# MMC_2_4_Ethernet.net
KiCad netlist of a schematic drawn in Altium Designer
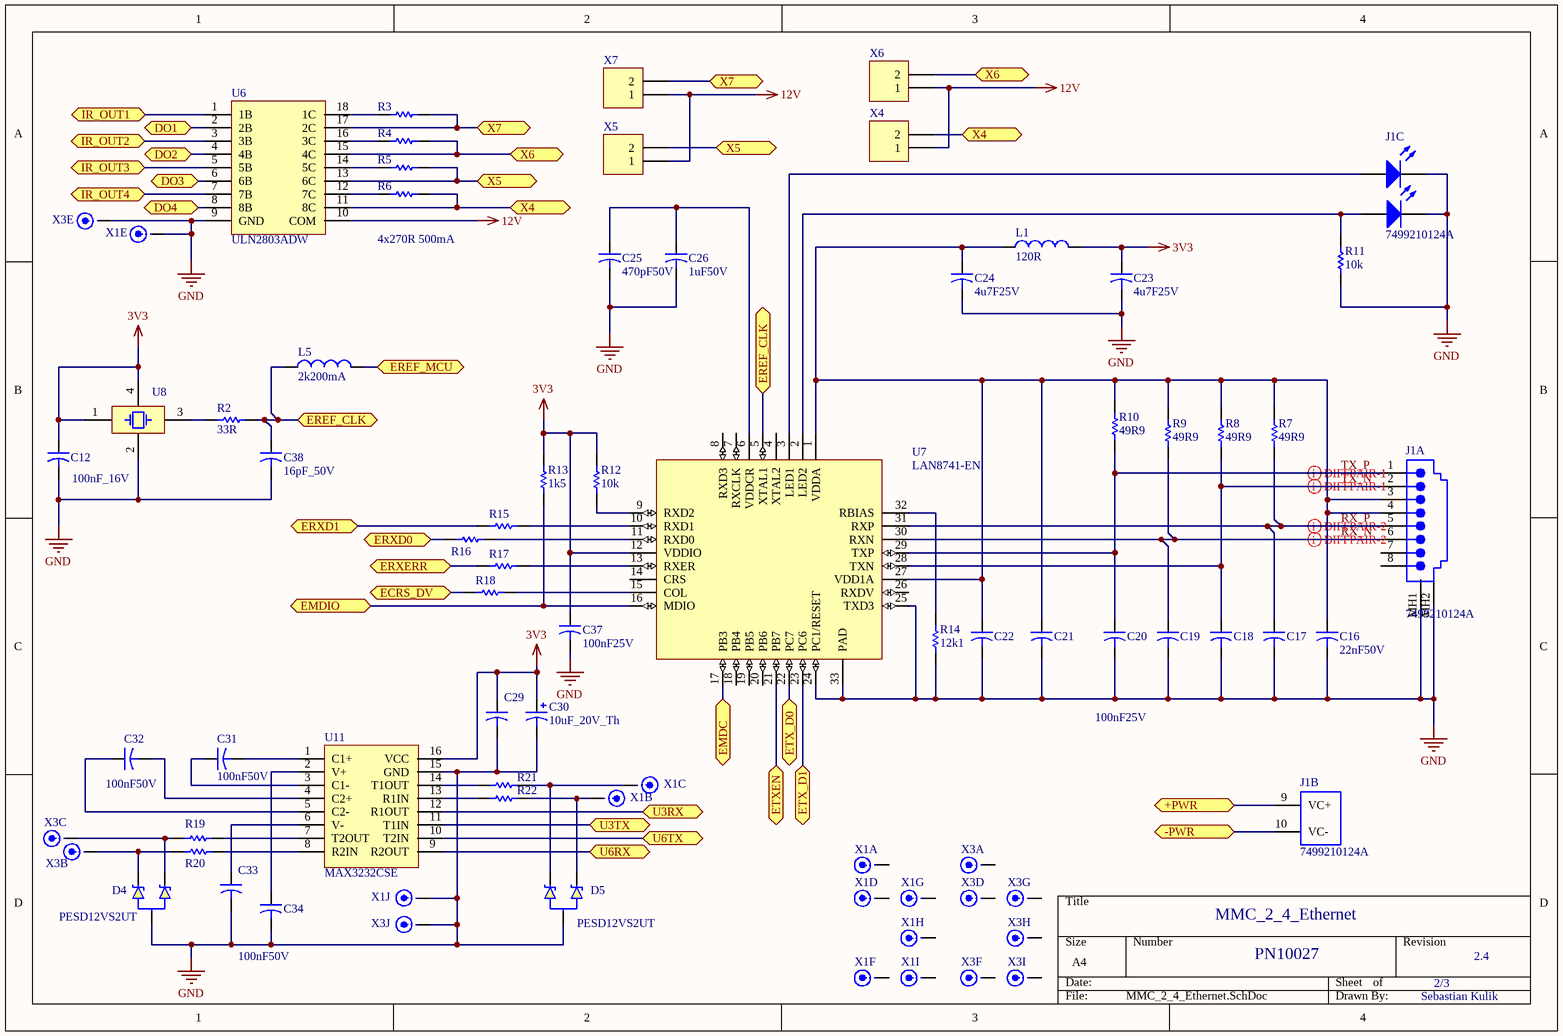
[diagram p0: MMC_2_4_Ethernet.SchDoc]

(export (version "E")
  (design (tool "Eeschema 10.0.6"))
  (components
    (comp (ref "C12")
      (value "100nF_16V")
      (footprint "C0402")
      (description "TDK. CGA series, X7R, 10%, 16V")
      (fields
        (field (name "MANUFACTURER") "TDK")
        (field (name "Comment") "100nF16V_0402")
        (field (name "PUBLISHER") "Sebastian Kulik")
      )
      (libsource (lib "Capacitors") (part "100nF16V_0402"))
    )
    (comp (ref "C16")
      (value "22nF50V")
      (footprint "C0603")
      (description "AVX ,  X7R, 5%, 50V")
      (fields
        (field (name "MANUFACTURER") "AVX")
        (field (name "Comment") "22nF50V_0603")
        (field (name "PUBLISHER") "Sebastian Kulik")
      )
      (libsource (lib "Capacitors") (part "22nF50V_0603"))
    )
    (comp (ref "C17")
      (value "10pF50V_0603")
      (footprint "C0603")
      (description "AVX ,  +-0.5pF, 50V")
      (fields (field (name "MANUFACTURER") "AVX") (field (name "PUBLISHER") "Sebastian Kulik"))
      (libsource (lib "Capacitors") (part "10pF50V_0603"))
    )
    (comp (ref "C18")
      (value "10pF50V_0603")
      (footprint "C0603")
      (description "AVX ,  +-0.5pF, 50V")
      (fields (field (name "MANUFACTURER") "AVX") (field (name "PUBLISHER") "Sebastian Kulik"))
      (libsource (lib "Capacitors") (part "10pF50V_0603"))
    )
    (comp (ref "C19")
      (value "10pF50V_0603")
      (footprint "C0603")
      (description "AVX ,  +-0.5pF, 50V")
      (fields (field (name "MANUFACTURER") "AVX") (field (name "PUBLISHER") "Sebastian Kulik"))
      (libsource (lib "Capacitors") (part "10pF50V_0603"))
    )
    (comp (ref "C20")
      (value "10pF50V_0603")
      (footprint "C0603")
      (description "AVX ,  +-0.5pF, 50V")
      (fields (field (name "MANUFACTURER") "AVX") (field (name "PUBLISHER") "Sebastian Kulik"))
      (libsource (lib "Capacitors") (part "10pF50V_0603"))
    )
    (comp (ref "C21")
      (value "100nF25V")
      (footprint "C0402")
      (description "AVX, X5R, 10%, 25V")
      (fields
        (field (name "MANUFACTURER") "AVX")
        (field (name "Comment") "100nF25V_0402")
        (field (name "PUBLISHER") "Sebastian Kulik")
      )
      (libsource (lib "Capacitors") (part "100nF25V_0402"))
    )
    (comp (ref "C22")
      (value "100nF25V_0402")
      (footprint "C0402")
      (description "AVX, X5R, 10%, 25V")
      (fields (field (name "MANUFACTURER") "AVX") (field (name "PUBLISHER") "Sebastian Kulik"))
      (libsource (lib "Capacitors") (part "100nF25V_0402"))
    )
    (comp (ref "C23")
      (value "4u7F25V")
      (footprint "C0805")
      (description "TDK  C series, X7R, 10%, 25V")
      (fields
        (field (name "MANUFACTURER") "TDK")
        (field (name "Comment") "4u7F25V_0805")
        (field (name "PUBLISHER") "Sebastian Kulik")
      )
      (libsource (lib "Capacitors") (part "4u7F25V_0805"))
    )
    (comp (ref "C24")
      (value "4u7F25V")
      (footprint "C0805")
      (description "TDK  C series, X7R, 10%, 25V")
      (fields
        (field (name "MANUFACTURER") "TDK")
        (field (name "Comment") "4u7F25V_0805")
        (field (name "PUBLISHER") "Sebastian Kulik")
      )
      (libsource (lib "Capacitors") (part "4u7F25V_0805"))
    )
    (comp (ref "C25")
      (value "470pF50V")
      (footprint "C0402")
      (description "AVX, 50V")
      (fields
        (field (name "MANUFACTURER") "AVX")
        (field (name "Comment") "470pF50V_0402")
        (field (name "PUBLISHER") "Sebastian Kulik")
      )
      (libsource (lib "Capacitors") (part "470pF50V_0402"))
    )
    (comp (ref "C26")
      (value "1uF50V")
      (footprint "C0603")
      (description "C series, X5R, 10%")
      (fields
        (field (name "MANUFACTURER") "TDK")
        (field (name "Comment") "1uF50V_0603")
        (field (name "PUBLISHER") "Sebastian Kulik")
      )
      (libsource (lib "Capacitors") (part "1uF50V_0603"))
    )
    (comp (ref "C29")
      (value "100nF25V_0402")
      (footprint "C0402")
      (description "AVX, X5R, 10%, 25V")
      (fields (field (name "MANUFACTURER") "AVX") (field (name "PUBLISHER") "Sebastian Kulik"))
      (libsource (lib "Capacitors") (part "100nF25V_0402"))
    )
    (comp (ref "C30")
      (value "10uF_20V_Th")
      (footprint "Vishay293D-B")
      (description "293 series, tantal, 10%, 10V")
      (fields
        (field (name "MANUFACTURER") "Vishay")
        (field (name "Comment") "10uF_20V_V293D-B")
        (field (name "PUBLISHER") "Sebastian Kulik")
      )
      (libsource (lib "Capacitors") (part "10uF_20V_V293D-B"))
    )
    (comp (ref "C31")
      (value "100nF50V")
      (footprint "C0402")
      (description "C series, X5R, 10%, 50V")
      (fields
        (field (name "MANUFACTURER") "Murata")
        (field (name "Comment") "100n50V_0402")
        (field (name "PUBLISHER") "Sebastian Kulik")
      )
      (libsource (lib "Capacitors") (part "100n50V_0402"))
    )
    (comp (ref "C32")
      (value "100nF50V")
      (footprint "C0402")
      (description "C series, X5R, 10%, 50V")
      (fields
        (field (name "MANUFACTURER") "Murata")
        (field (name "Comment") "100n50V_0402")
        (field (name "PUBLISHER") "Sebastian Kulik")
      )
      (libsource (lib "Capacitors") (part "100n50V_0402"))
    )
    (comp (ref "C33")
      (value "100n50V_0402")
      (footprint "C0402")
      (description "C series, X5R, 10%, 50V")
      (fields (field (name "MANUFACTURER") "Murata") (field (name "PUBLISHER") "Sebastian Kulik"))
      (libsource (lib "Capacitors") (part "100n50V_0402"))
    )
    (comp (ref "C34")
      (value "100nF50V")
      (footprint "C0402")
      (description "C series, X5R, 10%, 50V")
      (fields
        (field (name "MANUFACTURER") "Murata")
        (field (name "Comment") "100n50V_0402")
        (field (name "PUBLISHER") "Sebastian Kulik")
      )
      (libsource (lib "Capacitors") (part "100n50V_0402"))
    )
    (comp (ref "C37")
      (value "100nF25V")
      (footprint "C0402")
      (description "AVX, X5R, 10%, 25V")
      (fields
        (field (name "MANUFACTURER") "AVX")
        (field (name "Comment") "100nF25V_0402")
        (field (name "PUBLISHER") "Sebastian Kulik")
      )
      (libsource (lib "Capacitors") (part "100nF25V_0402"))
    )
    (comp (ref "C38")
      (value "16pF_50V")
      (footprint "C0402")
      (description "C series, 5%, 50V")
      (fields
        (field (name "MANUFACTURER") "Kemet")
        (field (name "Comment") "16pF50V_0402")
        (field (name "PUBLISHER") "Sebastian Kulik")
      )
      (libsource (lib "Capacitors") (part "16pF50V_0402"))
    )
    (comp (ref "D4")
      (value "PESD12VS2UT")
      (footprint "SOT23_N")
      (description "EDS diode(s)")
      (fields (field (name "MANUFACTURER") "NXP") (field (name "PUBLISHER") "Sebastian Kulik"))
      (libsource (lib "Discrete") (part "PESD12VS2UT"))
    )
    (comp (ref "D5")
      (value "PESD12VS2UT")
      (footprint "SOT23_N")
      (description "EDS diode(s)")
      (fields (field (name "MANUFACTURER") "NXP") (field (name "PUBLISHER") "Sebastian Kulik"))
      (libsource (lib "Discrete") (part "PESD12VS2UT"))
    )
    (comp (ref "J1")
      (value "7499210124A")
      (footprint "7499210124A")
      (description "Modular Jack , Right Angle RJ-45, Low Profile")
      (fields (field (name "MANUFACTURER") "Wuerth Elektronik") (field (name "PUBLISHER") "Sebastian Kulik"))
      (libsource (lib "Connectors") (part "Ethernet, POE, WE7499210124A"))
    )
    (comp (ref "L1")
      (value "120R")
      (footprint "L0603")
      (description "Murata, Ferrit, 120Rx2A")
      (fields
        (field (name "MANUFACTURER") "Murata")
        (field (name "Comment") "120R4A_0603")
        (field (name "PUBLISHER") "Sebastian Kulik")
      )
      (libsource (lib "Passives") (part "120R4A_0603"))
    )
    (comp (ref "L5")
      (value "2k200mA")
      (footprint "L0805_M")
      (description "Ferrit, 2k, 200mA")
      (fields
        (field (name "MANUFACTURER") "WE")
        (field (name "Comment") "2k200mA_0805")
        (field (name "PUBLISHER") "Sebastian Kulik")
      )
      (libsource (lib "Passives") (part "2k200mA_0805"))
    )
    (comp (ref "R2")
      (value "33R")
      (footprint "R0402")
      (description "Vishay CRCW series, 63mW, 1%")
      (fields
        (field (name "MANUFACTURER") "Vishay")
        (field (name "Comment") "33R_0402")
        (field (name "PUBLISHER") "Sebastian Kulik")
      )
      (libsource (lib "Resistors") (part "33R_0402"))
    )
    (comp (ref "R3")
      (value "270R_1210")
      (footprint "R1210_N")
      (description "ERJ series, 500mW, 5%")
      (fields (field (name "MANUFACTURER") "Panasonic") (field (name "PUBLISHER") "Sebastian Kulik"))
      (libsource (lib "Resistors") (part "270R_1210"))
    )
    (comp (ref "R4")
      (value "270R_1210")
      (footprint "R1210_N")
      (description "ERJ series, 500mW, 5%")
      (fields (field (name "MANUFACTURER") "Panasonic") (field (name "PUBLISHER") "Sebastian Kulik"))
      (libsource (lib "Resistors") (part "270R_1210"))
    )
    (comp (ref "R5")
      (value "270R_1210")
      (footprint "R1210_N")
      (description "ERJ series, 500mW, 5%")
      (fields (field (name "MANUFACTURER") "Panasonic") (field (name "PUBLISHER") "Sebastian Kulik"))
      (libsource (lib "Resistors") (part "270R_1210"))
    )
    (comp (ref "R6")
      (value "270R_1210")
      (footprint "R1210_N")
      (description "ERJ series, 500mW, 5%")
      (fields (field (name "MANUFACTURER") "Panasonic") (field (name "PUBLISHER") "Sebastian Kulik"))
      (libsource (lib "Resistors") (part "270R_1210"))
    )
    (comp (ref "R7")
      (value "49R9")
      (footprint "R0402")
      (description "Vishay CRCW series, 63mW, 1%")
      (fields
        (field (name "MANUFACTURER") "Vishay")
        (field (name "Comment") "49R9_0402")
        (field (name "PUBLISHER") "Sebastian Kulik")
      )
      (libsource (lib "Resistors") (part "49R9_0402"))
    )
    (comp (ref "R8")
      (value "49R9")
      (footprint "R0402")
      (description "Vishay CRCW series, 63mW, 1%")
      (fields
        (field (name "MANUFACTURER") "Vishay")
        (field (name "Comment") "49R9_0402")
        (field (name "PUBLISHER") "Sebastian Kulik")
      )
      (libsource (lib "Resistors") (part "49R9_0402"))
    )
    (comp (ref "R9")
      (value "49R9")
      (footprint "R0402")
      (description "Vishay CRCW series, 63mW, 1%")
      (fields
        (field (name "MANUFACTURER") "Vishay")
        (field (name "Comment") "49R9_0402")
        (field (name "PUBLISHER") "Sebastian Kulik")
      )
      (libsource (lib "Resistors") (part "49R9_0402"))
    )
    (comp (ref "R10")
      (value "49R9")
      (footprint "R0402")
      (description "Vishay CRCW series, 63mW, 1%")
      (fields
        (field (name "MANUFACTURER") "Vishay")
        (field (name "Comment") "49R9_0402")
        (field (name "PUBLISHER") "Sebastian Kulik")
      )
      (libsource (lib "Resistors") (part "49R9_0402"))
    )
    (comp (ref "R11")
      (value "10k")
      (footprint "R0402")
      (description "Vishay CRCW series, 125mW, 1%")
      (fields
        (field (name "MANUFACTURER") "Vishay")
        (field (name "Comment") "10k_0402")
        (field (name "PUBLISHER") "Sebastian Kulik")
      )
      (libsource (lib "Resistors") (part "10k_0402"))
    )
    (comp (ref "R12")
      (value "10k")
      (footprint "R0402")
      (description "Vishay CRCW series, 125mW, 1%")
      (fields
        (field (name "MANUFACTURER") "Vishay")
        (field (name "Comment") "10k_0402")
        (field (name "PUBLISHER") "Sebastian Kulik")
      )
      (libsource (lib "Resistors") (part "10k_0402"))
    )
    (comp (ref "R13")
      (value "1k5")
      (footprint "R0402")
      (description "Vishay CRCW series, 125mW, 1%")
      (fields
        (field (name "MANUFACTURER") "Vishay")
        (field (name "Comment") "1k5_0402")
        (field (name "PUBLISHER") "Sebastian Kulik")
      )
      (libsource (lib "Resistors") (part "1k5_0402"))
    )
    (comp (ref "R14")
      (value "12k1")
      (footprint "R0603(1608)")
      (description "Vishay, CRCW series, 100mW, 1%")
      (fields
        (field (name "MANUFACTURER") "Vishay")
        (field (name "Comment") "12k1_0603")
        (field (name "PUBLISHER") "Sebastian Kulik")
      )
      (libsource (lib "Resistors") (part "12k1_0603"))
    )
    (comp (ref "R15")
      (value "10R_0402")
      (footprint "R0402")
      (description "Vishay CRCW series, 125mW, 1%")
      (fields (field (name "MANUFACTURER") "Vishay") (field (name "PUBLISHER") "Sebastian Kulik"))
      (libsource (lib "Resistors") (part "10R_0402"))
    )
    (comp (ref "R16")
      (value "10R_0402")
      (footprint "R0402")
      (description "Vishay CRCW series, 125mW, 1%")
      (fields (field (name "MANUFACTURER") "Vishay") (field (name "PUBLISHER") "Sebastian Kulik"))
      (libsource (lib "Resistors") (part "10R_0402"))
    )
    (comp (ref "R17")
      (value "10R_0402")
      (footprint "R0402")
      (description "Vishay CRCW series, 125mW, 1%")
      (fields (field (name "MANUFACTURER") "Vishay") (field (name "PUBLISHER") "Sebastian Kulik"))
      (libsource (lib "Resistors") (part "10R_0402"))
    )
    (comp (ref "R18")
      (value "10R_0402")
      (footprint "R0402")
      (description "Vishay CRCW series, 125mW, 1%")
      (fields (field (name "MANUFACTURER") "Vishay") (field (name "PUBLISHER") "Sebastian Kulik"))
      (libsource (lib "Resistors") (part "10R_0402"))
    )
    (comp (ref "R19")
      (value "10R_0402")
      (footprint "R0402")
      (description "Vishay CRCW series, 125mW, 1%")
      (fields (field (name "MANUFACTURER") "Vishay") (field (name "PUBLISHER") "Sebastian Kulik"))
      (libsource (lib "Resistors") (part "10R_0402"))
    )
    (comp (ref "R20")
      (value "10R_0402")
      (footprint "R0402")
      (description "Vishay CRCW series, 125mW, 1%")
      (fields (field (name "MANUFACTURER") "Vishay") (field (name "PUBLISHER") "Sebastian Kulik"))
      (libsource (lib "Resistors") (part "10R_0402"))
    )
    (comp (ref "R21")
      (value "10R_0402")
      (footprint "R0402")
      (description "Vishay CRCW series, 125mW, 1%")
      (fields (field (name "MANUFACTURER") "Vishay") (field (name "PUBLISHER") "Sebastian Kulik"))
      (libsource (lib "Resistors") (part "10R_0402"))
    )
    (comp (ref "R22")
      (value "10R_0402")
      (footprint "R0402")
      (description "Vishay CRCW series, 125mW, 1%")
      (fields (field (name "MANUFACTURER") "Vishay") (field (name "PUBLISHER") "Sebastian Kulik"))
      (libsource (lib "Resistors") (part "10R_0402"))
    )
    (comp (ref "U6")
      (value "ULN2803ADW")
      (footprint "SOIC18-WIDE")
      (description "Darlington array, 50V")
      (fields (field (name "MANUFACTURER") "TI") (field (name "PUBLISHER") "Sebastian Kulik"))
      (libsource (lib "ICs") (part "ULN2803ADW"))
    )
    (comp (ref "U7")
      (value "LAN8741-EN")
      (footprint "32M1-A_M")
      (description "Ethernet Phy")
      (fields (field (name "MANUFACTURER") "Microchip") (field (name "PUBLISHER") "Sebastian Kulik"))
      (libsource (lib "ICs") (part "LAN8741-EN"))
    )
    (comp (ref "U8")
      (value "SG - 211 S*E -50.000M")
      (footprint "SG - 211 S*E")
      (description "Crystal")
      (fields (field (name "MANUFACTURER") "Epson") (field (name "PUBLISHER") "Sebastian Kulik"))
      (libsource (lib "ICs") (part "SG - 211 S*E -50.000M"))
    )
    (comp (ref "U11")
      (value "MAX3232CSE")
      (footprint "SOIC16_L")
      (description "RS232 transceiver")
      (fields (field (name "MANUFACTURER") "Maxim") (field (name "PUBLISHER") "Sebastian Kulik"))
      (libsource (lib "ICs") (part "MAX3232CSE"))
    )
    (comp (ref "X1")
      (value "SUB-D_9")
      (footprint "M09HP")
      (fields (field (name "MANUFACTURER") "AMP") (field (name "PUBLISHER") "Sebastian Kulik"))
      (libsource (lib "Connectors") (part "SUB-D_9"))
    )
    (comp (ref "X3")
      (value "SUB-D_9")
      (footprint "M09HP")
      (fields (field (name "MANUFACTURER") "AMP") (field (name "PUBLISHER") "Sebastian Kulik"))
      (libsource (lib "Connectors") (part "SUB-D_9"))
    )
    (comp (ref "X4")
      (value "WR-TBL3127")
      (footprint "WR-TBL-3127")
      (description "Header 2 pin, horizontal,WR-TBL3127")
      (fields (field (name "MANUFACTURER") "WE") (field (name "PUBLISHER") "Sebastian Kulik"))
      (libsource (lib "Connectors") (part "Header-2-WR-TBL3127"))
    )
    (comp (ref "X5")
      (value "WR-TBL3127")
      (footprint "WR-TBL-3127")
      (description "Header 2 pin, horizontal,WR-TBL3127")
      (fields (field (name "MANUFACTURER") "WE") (field (name "PUBLISHER") "Sebastian Kulik"))
      (libsource (lib "Connectors") (part "Header-2-WR-TBL3127"))
    )
    (comp (ref "X6")
      (value "WR-TBL3127")
      (footprint "WR-TBL-3127")
      (description "Header 2 pin, horizontal,WR-TBL3127")
      (fields (field (name "MANUFACTURER") "WE") (field (name "PUBLISHER") "Sebastian Kulik"))
      (libsource (lib "Connectors") (part "Header-2-WR-TBL3127"))
    )
    (comp (ref "X7")
      (value "WR-TBL3127")
      (footprint "WR-TBL-3127")
      (description "Header 2 pin, horizontal,WR-TBL3127")
      (fields (field (name "MANUFACTURER") "WE") (field (name "PUBLISHER") "Sebastian Kulik"))
      (libsource (lib "Connectors") (part "Header-2-WR-TBL3127"))
    )
  )
  (nets
    (net (code "1") (name "/+PWR") (class "Default")
      (node (ref "J1") (pin "9") (pinfunction "VC+_9") (pintype "passive"))
    )
    (net (code "2") (name "/-PWR") (class "Default")
      (node (ref "J1") (pin "10") (pinfunction "VC-_10") (pintype "passive"))
    )
    (net (code "3") (name "/DO1") (class "Default")
      (node (ref "U6") (pin "2") (pinfunction "2B_2") (pintype "passive"))
    )
    (net (code "4") (name "/DO2") (class "Default")
      (node (ref "U6") (pin "4") (pinfunction "4B_4") (pintype "passive"))
    )
    (net (code "5") (name "/DO3") (class "Default")
      (node (ref "U6") (pin "6") (pinfunction "6B_6") (pintype "passive"))
    )
    (net (code "6") (name "/DO4") (class "Default")
      (node (ref "U6") (pin "8") (pinfunction "8B_8") (pintype "passive"))
    )
    (net (code "7") (name "/ECRS_DV") (class "Default")
      (node (ref "R18") (pin "2") (pinfunction "2_2") (pintype "passive"))
    )
    (net (code "8") (name "/EMDC") (class "Default")
      (node (ref "U7") (pin "17") (pinfunction "PB3_17") (pintype "bidirectional"))
    )
    (net (code "9") (name "/EMDIO") (class "Default")
      (node (ref "R13") (pin "1") (pinfunction "1_1") (pintype "passive"))
      (node (ref "U7") (pin "16") (pinfunction "MDIO_16") (pintype "bidirectional"))
    )
    (net (code "10") (name "/EREF_CLK") (class "Default")
      (node (ref "C38") (pin "1") (pinfunction "1_1") (pintype "passive"))
      (node (ref "L5") (pin "1") (pinfunction "1_1") (pintype "passive"))
      (node (ref "R2") (pin "2") (pinfunction "2_2") (pintype "passive"))
      (node (ref "U7") (pin "5") (pinfunction "XTAL1_5") (pintype "bidirectional"))
    )
    (net (code "11") (name "/EREF_MCU") (class "Default")
      (node (ref "L5") (pin "2") (pinfunction "2_2") (pintype "passive"))
    )
    (net (code "12") (name "/ERXD0") (class "Default")
      (node (ref "R16") (pin "2") (pinfunction "2_2") (pintype "passive"))
    )
    (net (code "13") (name "/ERXD1") (class "Default")
      (node (ref "R15") (pin "2") (pinfunction "2_2") (pintype "passive"))
    )
    (net (code "14") (name "/ERXERR") (class "Default")
      (node (ref "R17") (pin "2") (pinfunction "2_2") (pintype "passive"))
    )
    (net (code "15") (name "/ETXEN") (class "Default")
      (node (ref "U7") (pin "21") (pinfunction "PB7_21") (pintype "bidirectional"))
    )
    (net (code "16") (name "/ETX_D0") (class "Default")
      (node (ref "U7") (pin "22") (pinfunction "PC7_22") (pintype "bidirectional"))
    )
    (net (code "17") (name "/ETX_D1") (class "Default")
      (node (ref "U7") (pin "23") (pinfunction "PC6_23") (pintype "bidirectional"))
    )
    (net (code "18") (name "/IR_OUT1") (class "Default")
      (node (ref "U6") (pin "1") (pinfunction "1B_1") (pintype "passive"))
    )
    (net (code "19") (name "/IR_OUT2") (class "Default")
      (node (ref "U6") (pin "3") (pinfunction "3B_3") (pintype "passive"))
    )
    (net (code "20") (name "/IR_OUT3") (class "Default")
      (node (ref "U6") (pin "5") (pinfunction "5B_5") (pintype "passive"))
    )
    (net (code "21") (name "/IR_OUT4") (class "Default")
      (node (ref "U6") (pin "7") (pinfunction "7B_7") (pintype "passive"))
    )
    (net (code "22") (name "/RX_N") (class "Default")
      (node (ref "C19") (pin "1") (pinfunction "1_1") (pintype "passive"))
      (node (ref "J1") (pin "6") (pinfunction "6_6") (pintype "passive"))
      (node (ref "R9") (pin "1") (pinfunction "1_1") (pintype "passive"))
      (node (ref "U7") (pin "30") (pinfunction "RXN_30") (pintype "passive"))
    )
    (net (code "23") (name "/RX_P") (class "Default")
      (node (ref "C17") (pin "1") (pinfunction "1_1") (pintype "passive"))
      (node (ref "J1") (pin "5") (pinfunction "5_5") (pintype "passive"))
      (node (ref "R7") (pin "1") (pinfunction "1_1") (pintype "passive"))
      (node (ref "U7") (pin "31") (pinfunction "RXP_31") (pintype "passive"))
    )
    (net (code "24") (name "/TX_N") (class "Default")
      (node (ref "C18") (pin "1") (pinfunction "1_1") (pintype "passive"))
      (node (ref "J1") (pin "2") (pinfunction "2_2") (pintype "passive"))
      (node (ref "R8") (pin "1") (pinfunction "1_1") (pintype "passive"))
      (node (ref "U7") (pin "28") (pinfunction "TXN_28") (pintype "bidirectional"))
    )
    (net (code "25") (name "/TX_P") (class "Default")
      (node (ref "C20") (pin "1") (pinfunction "1_1") (pintype "passive"))
      (node (ref "J1") (pin "1") (pinfunction "1_1") (pintype "passive"))
      (node (ref "R10") (pin "1") (pinfunction "1_1") (pintype "passive"))
      (node (ref "U7") (pin "29") (pinfunction "TXP_29") (pintype "bidirectional"))
    )
    (net (code "26") (name "/U3RX") (class "Default")
      (node (ref "U11") (pin "12") (pinfunction "R1OUT_12") (pintype "passive"))
    )
    (net (code "27") (name "/U3TX") (class "Default")
      (node (ref "U11") (pin "11") (pinfunction "T1IN_11") (pintype "passive"))
    )
    (net (code "28") (name "/U6RX") (class "Default")
      (node (ref "U11") (pin "9") (pinfunction "R2OUT_9") (pintype "passive"))
    )
    (net (code "29") (name "/U6TX") (class "Default")
      (node (ref "U11") (pin "10") (pinfunction "T2IN_10") (pintype "passive"))
    )
    (net (code "30") (name "/X4") (class "Default")
      (node (ref "R6") (pin "2") (pinfunction "2_2") (pintype "passive"))
      (node (ref "U6") (pin "11") (pinfunction "8C_11") (pintype "passive"))
      (node (ref "X4") (pin "2") (pinfunction "2_2") (pintype "passive"))
    )
    (net (code "31") (name "/X5") (class "Default")
      (node (ref "R5") (pin "2") (pinfunction "2_2") (pintype "passive"))
      (node (ref "U6") (pin "13") (pinfunction "6C_13") (pintype "passive"))
      (node (ref "X5") (pin "2") (pinfunction "2_2") (pintype "passive"))
    )
    (net (code "32") (name "/X6") (class "Default")
      (node (ref "R4") (pin "2") (pinfunction "2_2") (pintype "passive"))
      (node (ref "U6") (pin "15") (pinfunction "4C_15") (pintype "passive"))
      (node (ref "X6") (pin "2") (pinfunction "2_2") (pintype "passive"))
    )
    (net (code "33") (name "/X7") (class "Default")
      (node (ref "R3") (pin "2") (pinfunction "2_2") (pintype "passive"))
      (node (ref "U6") (pin "17") (pinfunction "2C_17") (pintype "passive"))
      (node (ref "X7") (pin "2") (pinfunction "2_2") (pintype "passive"))
    )
    (net (code "34") (name "3V3") (class "Default")
      (node (ref "C12") (pin "1") (pinfunction "1_1") (pintype "passive"))
      (node (ref "C23") (pin "1") (pinfunction "1_1") (pintype "passive"))
      (node (ref "C29") (pin "1") (pinfunction "1_1") (pintype "passive"))
      (node (ref "C30") (pin "1") (pinfunction "1_1") (pintype "passive"))
      (node (ref "C37") (pin "1") (pinfunction "1_1") (pintype "passive"))
      (node (ref "L1") (pin "2") (pinfunction "2_2") (pintype "passive"))
      (node (ref "R12") (pin "2") (pinfunction "2_2") (pintype "passive"))
      (node (ref "R13") (pin "2") (pinfunction "2_2") (pintype "passive"))
      (node (ref "U11") (pin "16") (pinfunction "VCC_16") (pintype "passive"))
      (node (ref "U7") (pin "12") (pinfunction "VDDIO_12") (pintype "passive"))
      (node (ref "U8") (pin "1") (pinfunction "E/D_1") (pintype "passive"))
      (node (ref "U8") (pin "4") (pinfunction "VCC_4") (pintype "passive"))
    )
    (net (code "35") (name "12V") (class "Default")
      (node (ref "U6") (pin "10") (pinfunction "COM_10") (pintype "passive"))
      (node (ref "X4") (pin "1") (pinfunction "1_1") (pintype "passive"))
      (node (ref "X5") (pin "1") (pinfunction "1_1") (pintype "passive"))
      (node (ref "X6") (pin "1") (pinfunction "1_1") (pintype "passive"))
      (node (ref "X7") (pin "1") (pinfunction "1_1") (pintype "passive"))
    )
    (net (code "36") (name "GND") (class "Default")
      (node (ref "C12") (pin "2") (pinfunction "2_2") (pintype "passive"))
      (node (ref "C16") (pin "2") (pinfunction "2_2") (pintype "passive"))
      (node (ref "C17") (pin "2") (pinfunction "2_2") (pintype "passive"))
      (node (ref "C18") (pin "2") (pinfunction "2_2") (pintype "passive"))
      (node (ref "C19") (pin "2") (pinfunction "2_2") (pintype "passive"))
      (node (ref "C20") (pin "2") (pinfunction "2_2") (pintype "passive"))
      (node (ref "C21") (pin "2") (pinfunction "2_2") (pintype "passive"))
      (node (ref "C22") (pin "2") (pinfunction "2_2") (pintype "passive"))
      (node (ref "C23") (pin "2") (pinfunction "2_2") (pintype "passive"))
      (node (ref "C24") (pin "2") (pinfunction "2_2") (pintype "passive"))
      (node (ref "C25") (pin "2") (pinfunction "2_2") (pintype "passive"))
      (node (ref "C26") (pin "2") (pinfunction "2_2") (pintype "passive"))
      (node (ref "C29") (pin "2") (pinfunction "2_2") (pintype "passive"))
      (node (ref "C30") (pin "2") (pinfunction "2_2") (pintype "passive"))
      (node (ref "C33") (pin "2") (pinfunction "2_2") (pintype "passive"))
      (node (ref "C34") (pin "2") (pinfunction "2_2") (pintype "passive"))
      (node (ref "C37") (pin "2") (pinfunction "2_2") (pintype "passive"))
      (node (ref "C38") (pin "2") (pinfunction "2_2") (pintype "passive"))
      (node (ref "D4") (pin "1") (pinfunction "A_1") (pintype "passive"))
      (node (ref "D5") (pin "1") (pinfunction "A_1") (pintype "passive"))
      (node (ref "J1") (pin "11") (pinfunction "K_11") (pintype "passive"))
      (node (ref "J1") (pin "13") (pinfunction "K_13") (pintype "passive"))
      (node (ref "J1") (pin "MH1") (pinfunction "Shield_MH1") (pintype "passive"))
      (node (ref "J1") (pin "MH2") (pinfunction "Shield_MH2") (pintype "passive"))
      (node (ref "R11") (pin "1") (pinfunction "1_1") (pintype "passive"))
      (node (ref "R14") (pin "1") (pinfunction "1_1") (pintype "passive"))
      (node (ref "U11") (pin "15") (pinfunction "GND_15") (pintype "passive"))
      (node (ref "U6") (pin "9") (pinfunction "GND_9") (pintype "passive"))
      (node (ref "U7") (pin "24") (pinfunction "PC1/RESET_24") (pintype "bidirectional"))
      (node (ref "U7") (pin "25") (pinfunction "TXD3_25") (pintype "bidirectional"))
      (node (ref "U7") (pin "33") (pinfunction "PAD_33") (pintype "power_in"))
      (node (ref "U8") (pin "2") (pinfunction "GND_2") (pintype "passive"))
      (node (ref "X1") (pin "10") (pinfunction "GND_10") (pintype "passive"))
      (node (ref "X1") (pin "5") (pintype "passive"))
      (node (ref "X3") (pin "10") (pinfunction "GND_10") (pintype "passive"))
      (node (ref "X3") (pin "5") (pintype "passive"))
    )
    (net (code "37") (name "Net-(D4-K1)") (class "Default")
      (node (ref "D4") (pin "3") (pinfunction "K1_3") (pintype "passive"))
      (node (ref "R19") (pin "1") (pinfunction "1_1") (pintype "passive"))
      (node (ref "X3") (pin "3") (pintype "passive"))
    )
    (net (code "38") (name "Net-(D4-K2)") (class "Default")
      (node (ref "D4") (pin "2") (pinfunction "K2_2") (pintype "passive"))
      (node (ref "R20") (pin "1") (pinfunction "1_1") (pintype "passive"))
      (node (ref "X3") (pin "2") (pintype "passive"))
    )
    (net (code "39") (name "Net-(D5-K1)") (class "Default")
      (node (ref "D5") (pin "3") (pinfunction "K1_3") (pintype "passive"))
      (node (ref "R22") (pin "2") (pinfunction "2_2") (pintype "passive"))
      (node (ref "X1") (pin "2") (pintype "passive"))
    )
    (net (code "40") (name "Net-(D5-K2)") (class "Default")
      (node (ref "D5") (pin "2") (pinfunction "K2_2") (pintype "passive"))
      (node (ref "R21") (pin "2") (pinfunction "2_2") (pintype "passive"))
      (node (ref "X1") (pin "3") (pintype "passive"))
    )
    (net (code "41") (name "Net-(U6-1C)") (class "Default")
      (node (ref "R3") (pin "1") (pinfunction "1_1") (pintype "passive"))
      (node (ref "U6") (pin "18") (pinfunction "1C_18") (pintype "passive"))
    )
    (net (code "42") (name "Net-(U6-3C)") (class "Default")
      (node (ref "R4") (pin "1") (pinfunction "1_1") (pintype "passive"))
      (node (ref "U6") (pin "16") (pinfunction "3C_16") (pintype "passive"))
    )
    (net (code "43") (name "Net-(U6-5C)") (class "Default")
      (node (ref "R5") (pin "1") (pinfunction "1_1") (pintype "passive"))
      (node (ref "U6") (pin "14") (pinfunction "5C_14") (pintype "passive"))
    )
    (net (code "44") (name "Net-(U6-7C)") (class "Default")
      (node (ref "R6") (pin "1") (pinfunction "1_1") (pintype "passive"))
      (node (ref "U6") (pin "12") (pinfunction "7C_12") (pintype "passive"))
    )
    (net (code "45") (name "Net-(U7-COL)") (class "Default")
      (node (ref "R18") (pin "1") (pinfunction "1_1") (pintype "passive"))
      (node (ref "U7") (pin "15") (pinfunction "COL_15") (pintype "passive"))
    )
    (net (code "46") (name "Net-(U7-LED1)") (class "Default")
      (node (ref "J1") (pin "12") (pinfunction "A_12") (pintype "passive"))
      (node (ref "U7") (pin "3") (pinfunction "LED1_3") (pintype "power_in"))
    )
    (net (code "47") (name "Net-(U7-LED2)") (class "Default")
      (node (ref "J1") (pin "14") (pinfunction "A_14") (pintype "passive"))
      (node (ref "R11") (pin "2") (pinfunction "2_2") (pintype "passive"))
      (node (ref "U7") (pin "2") (pinfunction "LED2_2") (pintype "passive"))
    )
    (net (code "48") (name "Net-(U7-RBIAS)") (class "Default")
      (node (ref "R14") (pin "2") (pinfunction "2_2") (pintype "passive"))
      (node (ref "U7") (pin "32") (pinfunction "RBIAS_32") (pintype "power_in"))
    )
    (net (code "49") (name "Net-(U7-RXD0)") (class "Default")
      (node (ref "R16") (pin "1") (pinfunction "1_1") (pintype "passive"))
      (node (ref "U7") (pin "11") (pinfunction "RXD0_11") (pintype "bidirectional"))
    )
    (net (code "50") (name "Net-(U7-RXD1)") (class "Default")
      (node (ref "R15") (pin "1") (pinfunction "1_1") (pintype "passive"))
      (node (ref "U7") (pin "10") (pinfunction "RXD1_10") (pintype "bidirectional"))
    )
    (net (code "51") (name "Net-(U7-RXD2)") (class "Default")
      (node (ref "R12") (pin "1") (pinfunction "1_1") (pintype "passive"))
      (node (ref "U7") (pin "9") (pinfunction "RXD2_9") (pintype "bidirectional"))
    )
    (net (code "52") (name "Net-(U7-RXER)") (class "Default")
      (node (ref "R17") (pin "1") (pinfunction "1_1") (pintype "passive"))
      (node (ref "U7") (pin "13") (pinfunction "RXER_13") (pintype "bidirectional"))
    )
    (net (code "53") (name "Net-(U7-VDD1A)") (class "Default")
      (node (ref "C16") (pin "1") (pinfunction "1_1") (pintype "passive"))
      (node (ref "C21") (pin "1") (pinfunction "1_1") (pintype "passive"))
      (node (ref "C22") (pin "1") (pinfunction "1_1") (pintype "passive"))
      (node (ref "C24") (pin "1") (pinfunction "1_1") (pintype "passive"))
      (node (ref "J1") (pin "3") (pinfunction "3_3") (pintype "passive"))
      (node (ref "J1") (pin "4") (pinfunction "4_4") (pintype "passive"))
      (node (ref "L1") (pin "1") (pinfunction "1_1") (pintype "passive"))
      (node (ref "R10") (pin "2") (pinfunction "2_2") (pintype "passive"))
      (node (ref "R7") (pin "2") (pinfunction "2_2") (pintype "passive"))
      (node (ref "R8") (pin "2") (pinfunction "2_2") (pintype "passive"))
      (node (ref "R9") (pin "2") (pinfunction "2_2") (pintype "passive"))
      (node (ref "U7") (pin "1") (pinfunction "VDDA_1") (pintype "passive"))
      (node (ref "U7") (pin "27") (pinfunction "VDD1A_27") (pintype "passive"))
    )
    (net (code "54") (name "Net-(U7-VDDCR)") (class "Default")
      (node (ref "C25") (pin "1") (pinfunction "1_1") (pintype "passive"))
      (node (ref "C26") (pin "1") (pinfunction "1_1") (pintype "passive"))
      (node (ref "U7") (pin "6") (pinfunction "VDDCR_6") (pintype "passive"))
    )
    (net (code "55") (name "Net-(U8-OSC2)") (class "Default")
      (node (ref "R2") (pin "1") (pinfunction "1_1") (pintype "passive"))
      (node (ref "U8") (pin "3") (pinfunction "OSC2_3") (pintype "passive"))
    )
    (net (code "56") (name "Net-(U11-C1+)") (class "Default")
      (node (ref "C31") (pin "2") (pinfunction "2_2") (pintype "passive"))
      (node (ref "U11") (pin "1") (pinfunction "C1+_1") (pintype "passive"))
    )
    (net (code "57") (name "Net-(U11-C1-)") (class "Default")
      (node (ref "C31") (pin "1") (pinfunction "1_1") (pintype "passive"))
      (node (ref "U11") (pin "3") (pinfunction "C1-_3") (pintype "passive"))
    )
    (net (code "58") (name "Net-(U11-C2+)") (class "Default")
      (node (ref "C32") (pin "2") (pinfunction "2_2") (pintype "passive"))
      (node (ref "U11") (pin "4") (pinfunction "C2+_4") (pintype "passive"))
    )
    (net (code "59") (name "Net-(U11-C2-)") (class "Default")
      (node (ref "C32") (pin "1") (pinfunction "1_1") (pintype "passive"))
      (node (ref "U11") (pin "5") (pinfunction "C2-_5") (pintype "passive"))
    )
    (net (code "60") (name "Net-(U11-R1IN)") (class "Default")
      (node (ref "R22") (pin "1") (pinfunction "1_1") (pintype "passive"))
      (node (ref "U11") (pin "13") (pinfunction "R1IN_13") (pintype "passive"))
    )
    (net (code "61") (name "Net-(U11-R2IN)") (class "Default")
      (node (ref "R20") (pin "2") (pinfunction "2_2") (pintype "passive"))
      (node (ref "U11") (pin "8") (pinfunction "R2IN_8") (pintype "passive"))
    )
    (net (code "62") (name "Net-(U11-T1OUT)") (class "Default")
      (node (ref "R21") (pin "1") (pinfunction "1_1") (pintype "passive"))
      (node (ref "U11") (pin "14") (pinfunction "T1OUT_14") (pintype "passive"))
    )
    (net (code "63") (name "Net-(U11-T2OUT)") (class "Default")
      (node (ref "R19") (pin "2") (pinfunction "2_2") (pintype "passive"))
      (node (ref "U11") (pin "7") (pinfunction "T2OUT_7") (pintype "passive"))
    )
    (net (code "64") (name "Net-(U11-V+)") (class "Default")
      (node (ref "C34") (pin "1") (pinfunction "1_1") (pintype "passive"))
      (node (ref "U11") (pin "2") (pinfunction "V+_2") (pintype "passive"))
    )
    (net (code "65") (name "Net-(U11-V-)") (class "Default")
      (node (ref "C33") (pin "1") (pinfunction "1_1") (pintype "passive"))
      (node (ref "U11") (pin "6") (pinfunction "V-_6") (pintype "passive"))
    )
    (net (code "66") (name "unconnected-(J1-Pad7)") (class "Default")
      (node (ref "J1") (pin "7") (pinfunction "7_7") (pintype "passive"))
    )
    (net (code "67") (name "unconnected-(J1-Pad8)") (class "Default")
      (node (ref "J1") (pin "8") (pinfunction "8_8") (pintype "passive"))
    )
    (net (code "68") (name "unconnected-(U7-CRS-Pad14)") (class "Default")
      (node (ref "U7") (pin "14") (pinfunction "CRS_14") (pintype "passive"))
    )
    (net (code "69") (name "unconnected-(U7-PB4-Pad18)") (class "Default")
      (node (ref "U7") (pin "18") (pinfunction "PB4_18") (pintype "bidirectional"))
    )
    (net (code "70") (name "unconnected-(U7-PB5-Pad19)") (class "Default")
      (node (ref "U7") (pin "19") (pinfunction "PB5_19") (pintype "bidirectional"))
    )
    (net (code "71") (name "unconnected-(U7-PB6-Pad20)") (class "Default")
      (node (ref "U7") (pin "20") (pinfunction "PB6_20") (pintype "bidirectional"))
    )
    (net (code "72") (name "unconnected-(U7-RXCLK-Pad7)") (class "Default")
      (node (ref "U7") (pin "7") (pinfunction "RXCLK_7") (pintype "bidirectional"))
    )
    (net (code "73") (name "unconnected-(U7-RXD3-Pad8)") (class "Default")
      (node (ref "U7") (pin "8") (pinfunction "RXD3_8") (pintype "bidirectional"))
    )
    (net (code "74") (name "unconnected-(U7-RXDV-Pad26)") (class "Default")
      (node (ref "U7") (pin "26") (pinfunction "RXDV_26") (pintype "bidirectional"))
    )
    (net (code "75") (name "unconnected-(U7-XTAL2-Pad4)") (class "Default")
      (node (ref "U7") (pin "4") (pinfunction "XTAL2_4") (pintype "power_in"))
    )
    (net (code "76") (name "unconnected-(X1-Pad1)") (class "Default")
      (node (ref "X1") (pin "1") (pintype "passive"))
    )
    (net (code "77") (name "unconnected-(X1-Pad4)") (class "Default")
      (node (ref "X1") (pin "4") (pintype "passive"))
    )
    (net (code "78") (name "unconnected-(X1-Pad6)") (class "Default")
      (node (ref "X1") (pin "6") (pintype "passive"))
    )
    (net (code "79") (name "unconnected-(X1-Pad7)") (class "Default")
      (node (ref "X1") (pin "7") (pintype "passive"))
    )
    (net (code "80") (name "unconnected-(X1-Pad8)") (class "Default")
      (node (ref "X1") (pin "8") (pintype "passive"))
    )
    (net (code "81") (name "unconnected-(X1-Pad9)") (class "Default")
      (node (ref "X1") (pin "9") (pintype "passive"))
    )
    (net (code "82") (name "unconnected-(X3-Pad1)") (class "Default")
      (node (ref "X3") (pin "1") (pintype "passive"))
    )
    (net (code "83") (name "unconnected-(X3-Pad4)") (class "Default")
      (node (ref "X3") (pin "4") (pintype "passive"))
    )
    (net (code "84") (name "unconnected-(X3-Pad6)") (class "Default")
      (node (ref "X3") (pin "6") (pintype "passive"))
    )
    (net (code "85") (name "unconnected-(X3-Pad7)") (class "Default")
      (node (ref "X3") (pin "7") (pintype "passive"))
    )
    (net (code "86") (name "unconnected-(X3-Pad8)") (class "Default")
      (node (ref "X3") (pin "8") (pintype "passive"))
    )
    (net (code "87") (name "unconnected-(X3-Pad9)") (class "Default")
      (node (ref "X3") (pin "9") (pintype "passive"))
    )
  )
)
